# POWER.net
KiCad netlist of a schematic drawn in Altium Designer
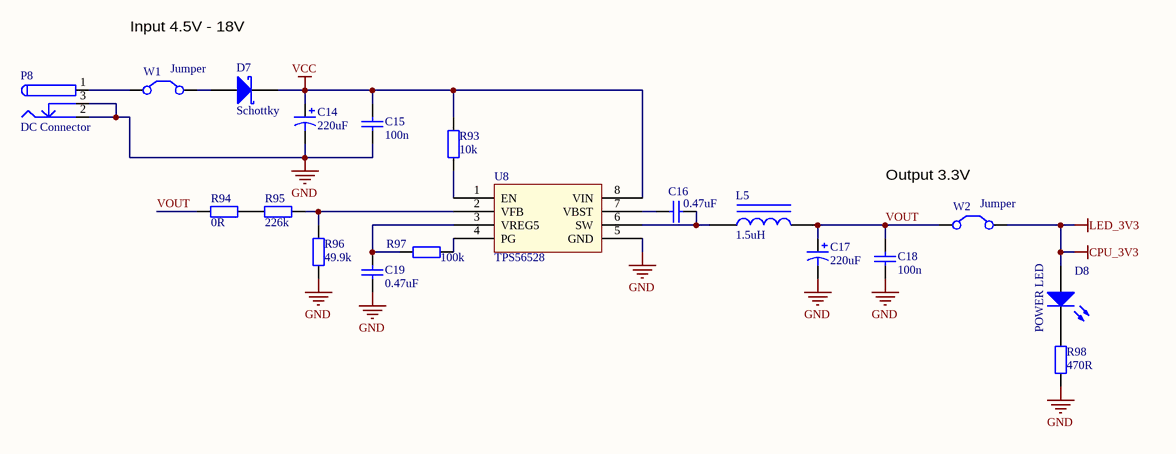
[diagram p0: POWER.SchDoc]

(export (version "E")
  (design (tool "Eeschema 10.0.6"))
  (components
    (comp (ref "C14")
      (value "220uF")
      (footprint "SMD CAPACITOR 220uF")
      (description "Capacitor")
      (fields (field (name "PUBLISHER") "Altium Limited"))
      (libsource (lib "Miscellaneous Devices") (part "Cap Pol1"))
    )
    (comp (ref "C15")
      (value "100n")
      (footprint "1608[0603]")
      (description "Capacitor")
      (fields (field (name "PUBLISHER") "Altium Limited"))
      (libsource (lib "Miscellaneous Devices") (part "Cap"))
    )
    (comp (ref "C16")
      (value "0.47uF")
      (footprint "1608[0603]")
      (description "Capacitor")
      (fields (field (name "PUBLISHER") "Altium Limited"))
      (libsource (lib "Miscellaneous Devices") (part "Cap"))
    )
    (comp (ref "C17")
      (value "220uF")
      (footprint "SMD CAPACITOR 220uF")
      (description "Capacitor")
      (fields (field (name "PUBLISHER") "Altium Limited"))
      (libsource (lib "Miscellaneous Devices") (part "Cap Pol1"))
    )
    (comp (ref "C18")
      (value "100n")
      (footprint "1608[0603]")
      (description "Capacitor")
      (fields (field (name "PUBLISHER") "Altium Limited"))
      (libsource (lib "Miscellaneous Devices") (part "Cap"))
    )
    (comp (ref "C19")
      (value "0.47uF")
      (footprint "1608[0603]")
      (description "Capacitor")
      (fields (field (name "PUBLISHER") "Altium Limited"))
      (libsource (lib "Miscellaneous Devices") (part "Cap"))
    )
    (comp (ref "D7")
      (value "Schottky")
      (footprint "SMB")
      (description "Schottky Diode")
      (fields (field (name "PUBLISHER") "Altium Limited"))
      (libsource (lib "Miscellaneous Devices") (part "D Schottky"))
    )
    (comp (ref "D8")
      (value "POWER LED")
      (footprint "LED-1")
      (description "Typical INFRARED GaAs LED")
      (fields (field (name "PUBLISHER") "Altium Limited"))
      (libsource (lib "Miscellaneous Devices") (part "LED0"))
    )
    (comp (ref "L5")
      (value "1.5uH")
      (footprint "Inductor")
      (description "Magnetic-Core Inductor")
      (fields (field (name "PUBLISHER") "Altium Limited"))
      (libsource (lib "Miscellaneous Devices") (part "Inductor Iron"))
    )
    (comp (ref "P8")
      (value "DC Connector")
      (footprint "DC Connector")
      (description "DC Power Connector")
      (libsource (lib "LukaLIBRARY") (part "DC Connector"))
    )
    (comp (ref "R93")
      (value "10k")
      (footprint "1608[0603]")
      (description "Resistor")
      (fields (field (name "PUBLISHER") "Altium Limited"))
      (libsource (lib "") (part "Res2_1"))
    )
    (comp (ref "R94")
      (value "0R")
      (footprint "1608[0603]")
      (description "Resistor")
      (fields (field (name "PUBLISHER") "Altium Limited"))
      (libsource (lib "Miscellaneous Devices") (part "Res2"))
    )
    (comp (ref "R95")
      (value "226k")
      (footprint "1608[0603]")
      (description "Resistor")
      (fields (field (name "PUBLISHER") "Altium Limited"))
      (libsource (lib "Miscellaneous Devices") (part "Res2"))
    )
    (comp (ref "R96")
      (value "49.9k")
      (footprint "1608[0603]")
      (description "Resistor")
      (fields (field (name "PUBLISHER") "Altium Limited"))
      (libsource (lib "") (part "Res2_1"))
    )
    (comp (ref "R97")
      (value "100k")
      (footprint "1608[0603]")
      (description "Resistor")
      (fields (field (name "PUBLISHER") "Altium Limited"))
      (libsource (lib "Miscellaneous Devices") (part "Res2"))
    )
    (comp (ref "R98")
      (value "470R")
      (footprint "1608[0603]")
      (description "Resistor")
      (fields (field (name "PUBLISHER") "Altium Limited"))
      (libsource (lib "") (part "Res2_1"))
    )
    (comp (ref "U8")
      (value "TPS56528")
      (footprint "TPS56528")
      (description "Step-Down Converter 5A 4.5V-18V")
      (libsource (lib "LP_Lib") (part "TPS56528"))
    )
    (comp (ref "W1")
      (value "Jumper")
      (footprint "HDR1X2")
      (description "Jumper Wire")
      (fields (field (name "PUBLISHER") "Altium Limited"))
      (libsource (lib "Miscellaneous Devices") (part "Jumper"))
    )
    (comp (ref "W2")
      (value "Jumper")
      (footprint "HDR1X2")
      (description "Jumper Wire")
      (fields (field (name "PUBLISHER") "Altium Limited"))
      (libsource (lib "Miscellaneous Devices") (part "Jumper"))
    )
  )
  (nets
    (net (code "1") (name "/VOUT") (class "Default")
      (node (ref "C17") (pin "1") (pinfunction "1_1") (pintype "passive"))
      (node (ref "C18") (pin "1") (pinfunction "1_1") (pintype "passive"))
      (node (ref "L5") (pin "2") (pinfunction "2_2") (pintype "passive"))
      (node (ref "R94") (pin "2") (pinfunction "2_2") (pintype "passive"))
      (node (ref "W2") (pin "1") (pinfunction "C1_1") (pintype "passive"))
    )
    (net (code "2") (name "CPU_3V3") (class "Default")
      (node (ref "D8") (pin "1") (pinfunction "A_1") (pintype "passive"))
      (node (ref "W2") (pin "2") (pinfunction "C2_2") (pintype "passive"))
    )
    (net (code "3") (name "GND") (class "Default")
      (node (ref "C14") (pin "2") (pinfunction "2_2") (pintype "passive"))
      (node (ref "C15") (pin "2") (pinfunction "2_2") (pintype "passive"))
      (node (ref "C17") (pin "2") (pinfunction "2_2") (pintype "passive"))
      (node (ref "C18") (pin "2") (pinfunction "2_2") (pintype "passive"))
      (node (ref "C19") (pin "2") (pinfunction "2_2") (pintype "passive"))
      (node (ref "P8") (pin "2") (pinfunction "2_2") (pintype "power_in"))
      (node (ref "P8") (pin "3") (pinfunction "3_3") (pintype "power_in"))
      (node (ref "R96") (pin "1") (pinfunction "1_1") (pintype "passive"))
      (node (ref "R98") (pin "1") (pinfunction "1_1") (pintype "passive"))
      (node (ref "U8") (pin "5") (pinfunction "GND_5") (pintype "passive"))
    )
    (net (code "4") (name "Net-(D7-A)") (class "Default")
      (node (ref "D7") (pin "1") (pinfunction "A_1") (pintype "passive"))
      (node (ref "W1") (pin "2") (pinfunction "C2_2") (pintype "passive"))
    )
    (net (code "5") (name "Net-(D8-K)") (class "Default")
      (node (ref "D8") (pin "2") (pinfunction "K_2") (pintype "passive"))
      (node (ref "R98") (pin "2") (pinfunction "2_2") (pintype "passive"))
    )
    (net (code "6") (name "Net-(R94-Pad1)") (class "Default")
      (node (ref "R94") (pin "1") (pinfunction "1_1") (pintype "passive"))
      (node (ref "R95") (pin "2") (pinfunction "2_2") (pintype "passive"))
    )
    (net (code "7") (name "Net-(U8-EN)") (class "Default")
      (node (ref "R93") (pin "1") (pinfunction "1_1") (pintype "passive"))
      (node (ref "U8") (pin "1") (pinfunction "EN_1") (pintype "passive"))
    )
    (net (code "8") (name "Net-(U8-PG)") (class "Default")
      (node (ref "R97") (pin "1") (pinfunction "1_1") (pintype "passive"))
      (node (ref "U8") (pin "4") (pinfunction "PG_4") (pintype "passive"))
    )
    (net (code "9") (name "Net-(U8-SW)") (class "Default")
      (node (ref "C16") (pin "2") (pinfunction "2_2") (pintype "passive"))
      (node (ref "L5") (pin "1") (pinfunction "1_1") (pintype "passive"))
      (node (ref "U8") (pin "6") (pinfunction "SW_6") (pintype "passive"))
    )
    (net (code "10") (name "Net-(U8-VBST)") (class "Default")
      (node (ref "C16") (pin "1") (pinfunction "1_1") (pintype "passive"))
      (node (ref "U8") (pin "7") (pinfunction "VBST_7") (pintype "passive"))
    )
    (net (code "11") (name "Net-(U8-VFB)") (class "Default")
      (node (ref "R95") (pin "1") (pinfunction "1_1") (pintype "passive"))
      (node (ref "R96") (pin "2") (pinfunction "2_2") (pintype "passive"))
      (node (ref "U8") (pin "2") (pinfunction "VFB_2") (pintype "passive"))
    )
    (net (code "12") (name "Net-(U8-VREG5)") (class "Default")
      (node (ref "C19") (pin "1") (pinfunction "1_1") (pintype "passive"))
      (node (ref "R97") (pin "2") (pinfunction "2_2") (pintype "passive"))
      (node (ref "U8") (pin "3") (pinfunction "VREG5_3") (pintype "passive"))
    )
    (net (code "13") (name "Net-(W1-C1)") (class "Default")
      (node (ref "P8") (pin "1") (pinfunction "1_1") (pintype "power_in"))
      (node (ref "W1") (pin "1") (pinfunction "C1_1") (pintype "passive"))
    )
    (net (code "14") (name "VCC") (class "Default")
      (node (ref "C14") (pin "1") (pinfunction "1_1") (pintype "passive"))
      (node (ref "C15") (pin "1") (pinfunction "1_1") (pintype "passive"))
      (node (ref "D7") (pin "2") (pinfunction "K_2") (pintype "passive"))
      (node (ref "R93") (pin "2") (pinfunction "2_2") (pintype "passive"))
      (node (ref "U8") (pin "8") (pinfunction "VIN_8") (pintype "passive"))
    )
  )
)
